# QLA-Test.net
KiCad netlist of a schematic drawn in Altium Designer
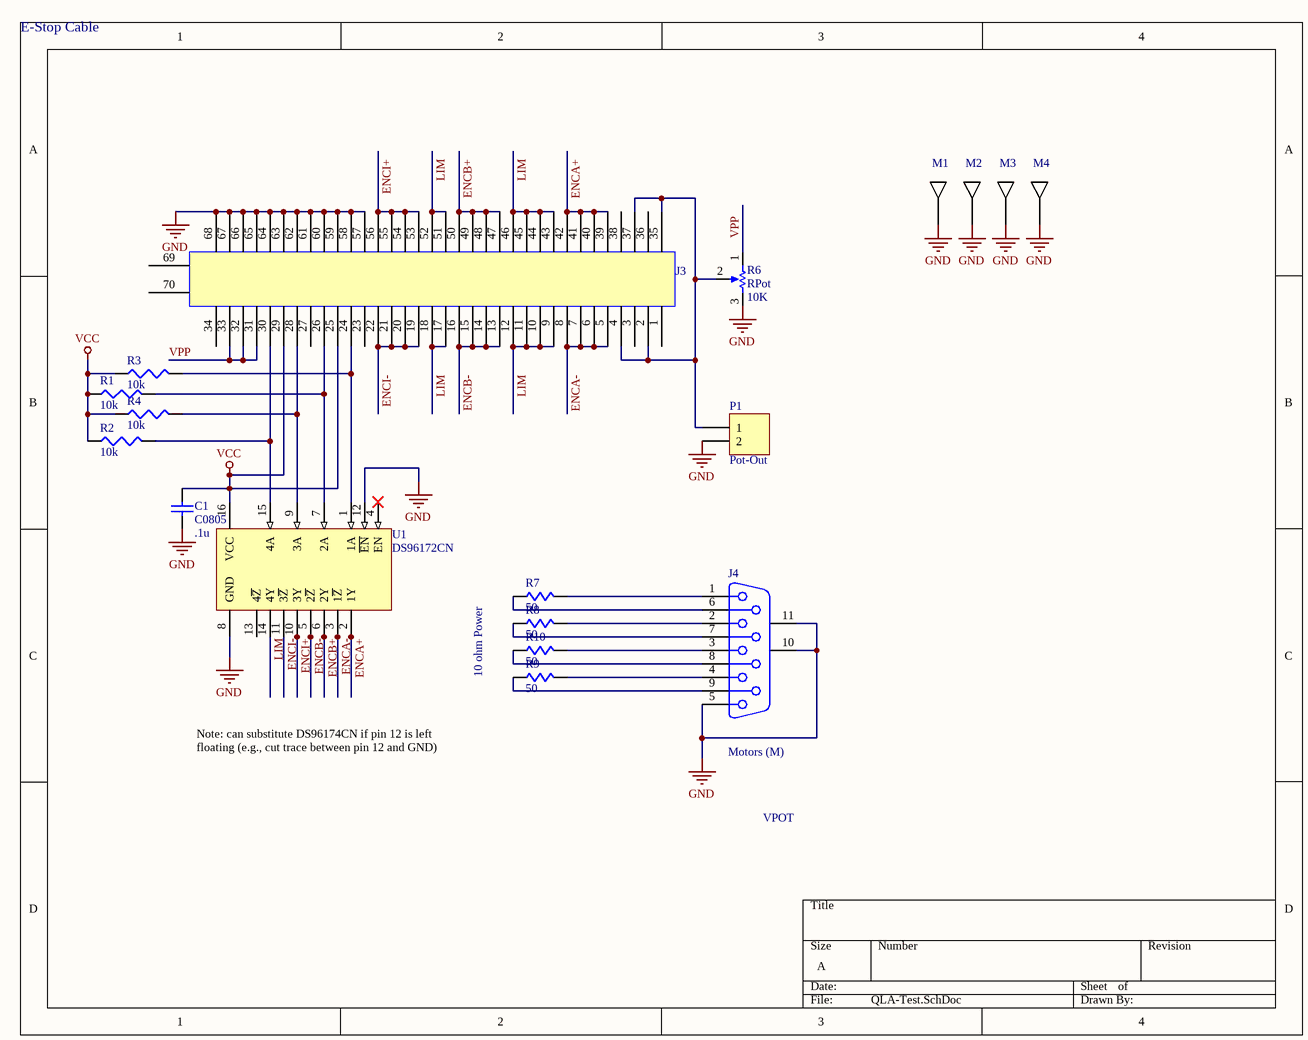
[diagram p0: QLA-Test.SchDoc]

(export (version "E")
  (design (tool "Eeschema 10.0.6"))
  (components
    (comp (ref "C1")
      (value "C0805")
      (footprint "0805")
      (description "Ceramic Chip Capacitor - Standard")
      (fields (field (name "ALTIUM_VALUE") ".1u") (field (name "PUBLISHER") "Altium Limited"))
      (libsource (lib "KEMET Chip Capacitor") (part "C0805"))
    )
    (comp (ref "J3")
      (value "HPDB68")
      (footprint "HPDB68FV")
      (description "Half Pitch D-Sub 68Pin")
      (libsource (lib "Snake-Connector") (part "HPDB68"))
    )
    (comp (ref "J4")
      (value "Sensor (M)")
      (footprint "DB9M")
      (description "Receptacle Assembly, 9 Position, Right Angle")
      (fields (field (name "MANUFACTURER") "Generic Components") (field (name "PUBLISHER") "Altium Limited"))
      (libsource (lib "Snake-Connector") (part "D Connector 9_1"))
    )
    (comp (ref "M1")
      (value "MHOLE")
      (footprint "MHOLE4")
      (description "Mounting Hole")
      (libsource (lib "QLA") (part "MHOLE"))
    )
    (comp (ref "M2")
      (value "MHOLE")
      (footprint "MHOLE4")
      (description "Mounting Hole")
      (libsource (lib "QLA") (part "MHOLE"))
    )
    (comp (ref "M3")
      (value "MHOLE")
      (footprint "MHOLE4")
      (description "Mounting Hole")
      (libsource (lib "QLA") (part "MHOLE"))
    )
    (comp (ref "M4")
      (value "MHOLE")
      (footprint "MHOLE4")
      (description "Mounting Hole")
      (libsource (lib "QLA") (part "MHOLE"))
    )
    (comp (ref "P1")
      (value "Pot-Out")
      (footprint "HDR1X2")
      (description "Header, 2-Pin")
      (fields (field (name "PUBLISHER") "Altium Limited"))
      (libsource (lib "Miscellaneous Connectors") (part "Header 2"))
    )
    (comp (ref "R1") (value "10k") (footprint "R0805") (libsource (lib "SnakeController") (part "R")))
    (comp (ref "R2") (value "10k") (footprint "R0805") (libsource (lib "SnakeController") (part "R")))
    (comp (ref "R3") (value "10k") (footprint "R0805") (libsource (lib "SnakeController") (part "R")))
    (comp (ref "R4") (value "10k") (footprint "R0805") (libsource (lib "SnakeController") (part "R")))
    (comp (ref "R6")
      (value "RPot")
      (footprint "VR5")
      (description "Potentiometer")
      (fields (field (name "ALTIUM_VALUE") "10K") (field (name "PUBLISHER") "Altium Limited"))
      (libsource (lib "Miscellaneous Devices") (part "RPot"))
    )
    (comp (ref "R7") (value "50") (footprint "TO-220AC") (libsource (lib "FPGA") (part "R")))
    (comp (ref "R8") (value "50") (footprint "TO-220AC") (libsource (lib "FPGA") (part "R")))
    (comp (ref "R9") (value "50") (footprint "TO-220AC") (libsource (lib "FPGA") (part "R")))
    (comp (ref "R10") (value "50") (footprint "TO-220AC") (libsource (lib "FPGA") (part "R")))
    (comp (ref "U1")
      (value "DS96172CN")
      (footprint "N16E")
      (description "RS-485/RS-422 Quad Differential Line Driver, 16-pin MDIP")
      (fields
        (field (name "PARTNUMBER") "DS96174CN")
        (field (name "MANUFACTURER") "National Semiconductor")
        (field (name "PUBLISHER") "Altium Limited")
      )
      (libsource (lib "NSC Interface") (part "DS96174CN"))
    )
  )
  (nets
    (net (code "1") (name "/ENCA+") (class "Default")
      (node (ref "J3") (pin "39") (pinfunction "39_39") (pintype "passive"))
      (node (ref "J3") (pin "40") (pinfunction "40_40") (pintype "passive"))
      (node (ref "J3") (pin "41") (pinfunction "41_41") (pintype "passive"))
      (node (ref "J3") (pin "42") (pinfunction "42_42") (pintype "passive"))
      (node (ref "U1") (pin "2") (pinfunction "1Y_2") (pintype "tri_state"))
    )
    (net (code "2") (name "/ENCA-") (class "Default")
      (node (ref "J3") (pin "5") (pinfunction "5_5") (pintype "passive"))
      (node (ref "J3") (pin "6") (pinfunction "6_6") (pintype "passive"))
      (node (ref "J3") (pin "7") (pinfunction "7_7") (pintype "passive"))
      (node (ref "J3") (pin "8") (pinfunction "8_8") (pintype "passive"))
      (node (ref "U1") (pin "3") (pinfunction "1~{Z}_3") (pintype "tri_state"))
    )
    (net (code "3") (name "/ENCB+") (class "Default")
      (node (ref "J3") (pin "47") (pinfunction "47_47") (pintype "passive"))
      (node (ref "J3") (pin "48") (pinfunction "48_48") (pintype "passive"))
      (node (ref "J3") (pin "49") (pinfunction "49_49") (pintype "passive"))
      (node (ref "J3") (pin "50") (pinfunction "50_50") (pintype "passive"))
      (node (ref "U1") (pin "6") (pinfunction "2Y_6") (pintype "tri_state"))
    )
    (net (code "4") (name "/ENCB-") (class "Default")
      (node (ref "J3") (pin "13") (pinfunction "13_13") (pintype "passive"))
      (node (ref "J3") (pin "14") (pinfunction "14_14") (pintype "passive"))
      (node (ref "J3") (pin "15") (pinfunction "15_15") (pintype "passive"))
      (node (ref "J3") (pin "16") (pinfunction "16_16") (pintype "passive"))
      (node (ref "U1") (pin "5") (pinfunction "2~{Z}_5") (pintype "tri_state"))
    )
    (net (code "5") (name "/ENCI+") (class "Default")
      (node (ref "J3") (pin "53") (pinfunction "53_53") (pintype "passive"))
      (node (ref "J3") (pin "54") (pinfunction "54_54") (pintype "passive"))
      (node (ref "J3") (pin "55") (pinfunction "55_55") (pintype "passive"))
      (node (ref "J3") (pin "56") (pinfunction "56_56") (pintype "passive"))
      (node (ref "U1") (pin "10") (pinfunction "3Y_10") (pintype "tri_state"))
    )
    (net (code "6") (name "/ENCI-") (class "Default")
      (node (ref "J3") (pin "19") (pinfunction "19_19") (pintype "passive"))
      (node (ref "J3") (pin "20") (pinfunction "20_20") (pintype "passive"))
      (node (ref "J3") (pin "21") (pinfunction "21_21") (pintype "passive"))
      (node (ref "J3") (pin "22") (pinfunction "22_22") (pintype "passive"))
      (node (ref "U1") (pin "11") (pinfunction "3~{Z}_11") (pintype "tri_state"))
    )
    (net (code "7") (name "/LIM") (class "Default")
      (node (ref "J3") (pin "10") (pinfunction "10_10") (pintype "passive"))
      (node (ref "J3") (pin "11") (pinfunction "11_11") (pintype "passive"))
      (node (ref "J3") (pin "12") (pinfunction "12_12") (pintype "passive"))
      (node (ref "J3") (pin "17") (pinfunction "17_17") (pintype "passive"))
      (node (ref "J3") (pin "18") (pinfunction "18_18") (pintype "passive"))
      (node (ref "J3") (pin "43") (pinfunction "43_43") (pintype "passive"))
      (node (ref "J3") (pin "44") (pinfunction "44_44") (pintype "passive"))
      (node (ref "J3") (pin "45") (pinfunction "45_45") (pintype "passive"))
      (node (ref "J3") (pin "46") (pinfunction "46_46") (pintype "passive"))
      (node (ref "J3") (pin "51") (pinfunction "51_51") (pintype "passive"))
      (node (ref "J3") (pin "52") (pinfunction "52_52") (pintype "passive"))
      (node (ref "J3") (pin "9") (pinfunction "9_9") (pintype "passive"))
      (node (ref "U1") (pin "14") (pinfunction "4Y_14") (pintype "tri_state"))
    )
    (net (code "8") (name "/VPP") (class "Default")
      (node (ref "J3") (pin "31") (pinfunction "31_31") (pintype "passive"))
      (node (ref "J3") (pin "32") (pinfunction "32_32") (pintype "passive"))
      (node (ref "J3") (pin "33") (pinfunction "33_33") (pintype "passive"))
      (node (ref "R6") (pin "1") (pinfunction "TOP_1") (pintype "passive"))
    )
    (net (code "9") (name "GND") (class "Default")
      (node (ref "C1") (pin "1") (pinfunction "1_1") (pintype "passive"))
      (node (ref "J3") (pin "57") (pinfunction "57_57") (pintype "passive"))
      (node (ref "J3") (pin "58") (pinfunction "58_58") (pintype "passive"))
      (node (ref "J3") (pin "59") (pinfunction "59_59") (pintype "passive"))
      (node (ref "J3") (pin "60") (pinfunction "60_60") (pintype "passive"))
      (node (ref "J3") (pin "61") (pinfunction "61_61") (pintype "passive"))
      (node (ref "J3") (pin "62") (pinfunction "62_62") (pintype "passive"))
      (node (ref "J3") (pin "63") (pinfunction "63_63") (pintype "passive"))
      (node (ref "J3") (pin "64") (pinfunction "64_64") (pintype "passive"))
      (node (ref "J3") (pin "65") (pinfunction "65_65") (pintype "passive"))
      (node (ref "J3") (pin "66") (pinfunction "66_66") (pintype "passive"))
      (node (ref "J3") (pin "67") (pinfunction "67_67") (pintype "passive"))
      (node (ref "J3") (pin "68") (pinfunction "68_68") (pintype "passive"))
      (node (ref "J4") (pin "10") (pinfunction "MH1_10") (pintype "passive"))
      (node (ref "J4") (pin "11") (pinfunction "MH2_11") (pintype "passive"))
      (node (ref "J4") (pin "5") (pinfunction "5_5") (pintype "passive"))
      (node (ref "M1") (pin "1") (pinfunction "1_1") (pintype "passive"))
      (node (ref "M2") (pin "1") (pinfunction "1_1") (pintype "passive"))
      (node (ref "M3") (pin "1") (pinfunction "1_1") (pintype "passive"))
      (node (ref "M4") (pin "1") (pinfunction "1_1") (pintype "passive"))
      (node (ref "P1") (pin "2") (pinfunction "2_2") (pintype "passive"))
      (node (ref "R6") (pin "3") (pinfunction "BOT_3") (pintype "passive"))
      (node (ref "U1") (pin "12") (pinfunction "~{EN}_12") (pintype "input"))
      (node (ref "U1") (pin "8") (pinfunction "GND_8") (pintype "power_in"))
    )
    (net (code "10") (name "Net-(J4-Pad1)") (class "Default")
      (node (ref "J4") (pin "1") (pinfunction "1_1") (pintype "passive"))
      (node (ref "R7") (pin "2") (pinfunction "2_2") (pintype "passive"))
    )
    (net (code "11") (name "Net-(J4-Pad2)") (class "Default")
      (node (ref "J4") (pin "2") (pinfunction "2_2") (pintype "passive"))
      (node (ref "R8") (pin "2") (pinfunction "2_2") (pintype "passive"))
    )
    (net (code "12") (name "Net-(J4-Pad3)") (class "Default")
      (node (ref "J4") (pin "3") (pinfunction "3_3") (pintype "passive"))
      (node (ref "R10") (pin "2") (pinfunction "2_2") (pintype "passive"))
    )
    (net (code "13") (name "Net-(J4-Pad4)") (class "Default")
      (node (ref "J4") (pin "4") (pinfunction "4_4") (pintype "passive"))
      (node (ref "R9") (pin "2") (pinfunction "2_2") (pintype "passive"))
    )
    (net (code "14") (name "Net-(J4-Pad6)") (class "Default")
      (node (ref "J4") (pin "6") (pinfunction "6_6") (pintype "passive"))
      (node (ref "R7") (pin "1") (pinfunction "1_1") (pintype "passive"))
    )
    (net (code "15") (name "Net-(J4-Pad7)") (class "Default")
      (node (ref "J4") (pin "7") (pinfunction "7_7") (pintype "passive"))
      (node (ref "R8") (pin "1") (pinfunction "1_1") (pintype "passive"))
    )
    (net (code "16") (name "Net-(J4-Pad8)") (class "Default")
      (node (ref "J4") (pin "8") (pinfunction "8_8") (pintype "passive"))
      (node (ref "R10") (pin "1") (pinfunction "1_1") (pintype "passive"))
    )
    (net (code "17") (name "Net-(J4-Pad9)") (class "Default")
      (node (ref "J4") (pin "9") (pinfunction "9_9") (pintype "passive"))
      (node (ref "R9") (pin "1") (pinfunction "1_1") (pintype "passive"))
    )
    (net (code "18") (name "Net-(R6-TAP)") (class "Default")
      (node (ref "J3") (pin "2") (pinfunction "2_2") (pintype "passive"))
      (node (ref "J3") (pin "35") (pinfunction "35_35") (pintype "passive"))
      (node (ref "J3") (pin "37") (pinfunction "37_37") (pintype "passive"))
      (node (ref "J3") (pin "4") (pinfunction "4_4") (pintype "passive"))
      (node (ref "P1") (pin "1") (pinfunction "1_1") (pintype "passive"))
      (node (ref "R6") (pin "2") (pinfunction "TAP_2") (pintype "passive"))
    )
    (net (code "19") (name "Net-(U1-1A)") (class "Default")
      (node (ref "J3") (pin "24") (pinfunction "24_24") (pintype "passive"))
      (node (ref "R3") (pin "2") (pinfunction "2_2") (pintype "passive"))
      (node (ref "U1") (pin "1") (pinfunction "1A_1") (pintype "input"))
    )
    (net (code "20") (name "Net-(U1-2A)") (class "Default")
      (node (ref "J3") (pin "26") (pinfunction "26_26") (pintype "passive"))
      (node (ref "R1") (pin "2") (pinfunction "2_2") (pintype "passive"))
      (node (ref "U1") (pin "7") (pinfunction "2A_7") (pintype "input"))
    )
    (net (code "21") (name "Net-(U1-3A)") (class "Default")
      (node (ref "J3") (pin "28") (pinfunction "28_28") (pintype "passive"))
      (node (ref "R4") (pin "2") (pinfunction "2_2") (pintype "passive"))
      (node (ref "U1") (pin "9") (pinfunction "3A_9") (pintype "input"))
    )
    (net (code "22") (name "Net-(U1-4A)") (class "Default")
      (node (ref "J3") (pin "30") (pinfunction "30_30") (pintype "passive"))
      (node (ref "R2") (pin "2") (pinfunction "2_2") (pintype "passive"))
      (node (ref "U1") (pin "15") (pinfunction "4A_15") (pintype "input"))
    )
    (net (code "23") (name "VCC") (class "Default")
      (node (ref "C1") (pin "2") (pinfunction "2_2") (pintype "passive"))
      (node (ref "J3") (pin "25") (pinfunction "25_25") (pintype "passive"))
      (node (ref "J3") (pin "29") (pinfunction "29_29") (pintype "passive"))
      (node (ref "R1") (pin "1") (pinfunction "1_1") (pintype "passive"))
      (node (ref "R2") (pin "1") (pinfunction "1_1") (pintype "passive"))
      (node (ref "R3") (pin "1") (pinfunction "1_1") (pintype "passive"))
      (node (ref "R4") (pin "1") (pinfunction "1_1") (pintype "passive"))
      (node (ref "U1") (pin "16") (pinfunction "VCC_16") (pintype "power_in"))
    )
    (net (code "24") (name "unconnected-(J3-Pad1)") (class "Default")
      (node (ref "J3") (pin "1") (pinfunction "1_1") (pintype "passive"))
    )
    (net (code "25") (name "unconnected-(J3-Pad3)") (class "Default")
      (node (ref "J3") (pin "3") (pinfunction "3_3") (pintype "passive"))
    )
    (net (code "26") (name "unconnected-(J3-Pad23)") (class "Default")
      (node (ref "J3") (pin "23") (pinfunction "23_23") (pintype "passive"))
    )
    (net (code "27") (name "unconnected-(J3-Pad27)") (class "Default")
      (node (ref "J3") (pin "27") (pinfunction "27_27") (pintype "passive"))
    )
    (net (code "28") (name "unconnected-(J3-Pad34)") (class "Default")
      (node (ref "J3") (pin "34") (pinfunction "34_34") (pintype "passive"))
    )
    (net (code "29") (name "unconnected-(J3-Pad36)") (class "Default")
      (node (ref "J3") (pin "36") (pinfunction "36_36") (pintype "passive"))
    )
    (net (code "30") (name "unconnected-(J3-Pad38)") (class "Default")
      (node (ref "J3") (pin "38") (pinfunction "38_38") (pintype "passive"))
    )
    (net (code "31") (name "unconnected-(J3-Pad69)") (class "Default")
      (node (ref "J3") (pin "69") (pinfunction "69_69") (pintype "passive"))
    )
    (net (code "32") (name "unconnected-(J3-Pad70)") (class "Default")
      (node (ref "J3") (pin "70") (pinfunction "70_70") (pintype "passive"))
    )
    (net (code "33") (name "unconnected-(U1-4~{Z}-Pad13)") (class "Default")
      (node (ref "U1") (pin "13") (pinfunction "4~{Z}_13") (pintype "tri_state"))
    )
    (net (code "34") (name "unconnected-(U1-EN-Pad4)") (class "Default")
      (node (ref "U1") (pin "4") (pinfunction "EN_4") (pintype "input+no_connect"))
    )
  )
)
